# untitled.net
KiCad netlist of a schematic drawn in EAGLE
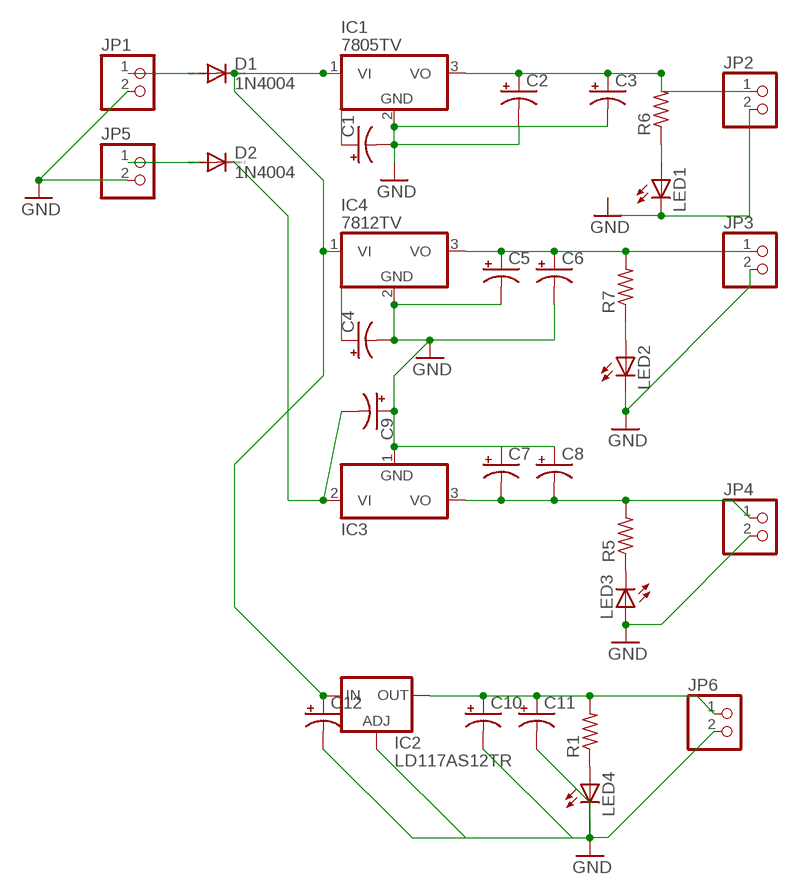
[diagram p0: schematic, sheet 1]

(export (version "E")
  (design (tool "Eeschema 10.0.6"))
  (components
    (comp (ref "C1")
      (value "CPOL-USE2.5-5")
      (footprint "eagle-import:E2,5-5")
      (libsource (lib "eagle-import") (part "CPOL-USE2.5-5"))
    )
    (comp (ref "C2")
      (value "CPOL-USE2.5-5")
      (footprint "eagle-import:E2,5-5")
      (libsource (lib "eagle-import") (part "CPOL-USE2.5-5"))
    )
    (comp (ref "C3")
      (value "CPOL-USE2.5-5")
      (footprint "eagle-import:E2,5-5")
      (libsource (lib "eagle-import") (part "CPOL-USE2.5-5"))
    )
    (comp (ref "C4")
      (value "CPOL-USE2.5-5")
      (footprint "eagle-import:E2,5-5")
      (libsource (lib "eagle-import") (part "CPOL-USE2.5-5"))
    )
    (comp (ref "C5")
      (value "CPOL-USE2.5-5")
      (footprint "eagle-import:E2,5-5")
      (libsource (lib "eagle-import") (part "CPOL-USE2.5-5"))
    )
    (comp (ref "C6")
      (value "CPOL-USE2.5-5")
      (footprint "eagle-import:E2,5-5")
      (libsource (lib "eagle-import") (part "CPOL-USE2.5-5"))
    )
    (comp (ref "C7")
      (value "CPOL-USE2.5-5")
      (footprint "eagle-import:E2,5-5")
      (libsource (lib "eagle-import") (part "CPOL-USE2.5-5"))
    )
    (comp (ref "C8")
      (value "CPOL-USE2.5-5")
      (footprint "eagle-import:E2,5-5")
      (libsource (lib "eagle-import") (part "CPOL-USE2.5-5"))
    )
    (comp (ref "C9")
      (value "CPOL-USE2.5-5")
      (footprint "eagle-import:E2,5-5")
      (libsource (lib "eagle-import") (part "CPOL-USE2.5-5"))
    )
    (comp (ref "C10")
      (value "CPOL-USE2.5-5")
      (footprint "eagle-import:E2,5-5")
      (libsource (lib "eagle-import") (part "CPOL-USE2.5-5"))
    )
    (comp (ref "C11")
      (value "CPOL-USE2.5-5")
      (footprint "eagle-import:E2,5-5")
      (libsource (lib "eagle-import") (part "CPOL-USE2.5-5"))
    )
    (comp (ref "C12")
      (value "CPOL-USE2.5-5")
      (footprint "eagle-import:E2,5-5")
      (libsource (lib "eagle-import") (part "CPOL-USE2.5-5"))
    )
    (comp (ref "D1")
      (value "1N4004")
      (footprint "eagle-import:DO41-10")
      (libsource (lib "eagle-import") (part "1N4004"))
    )
    (comp (ref "D2")
      (value "1N4004")
      (footprint "eagle-import:DO41-10")
      (libsource (lib "eagle-import") (part "1N4004"))
    )
    (comp (ref "IC1")
      (value "7805TV")
      (footprint "eagle-import:TO220V")
      (libsource (lib "eagle-import") (part "78TV05"))
    )
    (comp (ref "IC2")
      (value "LD117AS12TR")
      (footprint "eagle-import:SOT223")
      (libsource (lib "eagle-import") (part "LD117A?S12TR"))
    )
    (comp (ref "IC3")
      (value "7912T")
      (footprint "eagle-import:TO220H")
      (libsource (lib "eagle-import") (part "79T12"))
    )
    (comp (ref "IC4")
      (value "7812TV")
      (footprint "eagle-import:TO220V")
      (libsource (lib "eagle-import") (part "78TV12"))
    )
    (comp (ref "JP1")
      (value "PINHD-1X2")
      (footprint "eagle-import:1X02")
      (libsource (lib "eagle-import") (part "PINHD-1X2"))
    )
    (comp (ref "JP2")
      (value "PINHD-1X2")
      (footprint "eagle-import:1X02")
      (libsource (lib "eagle-import") (part "PINHD-1X2"))
    )
    (comp (ref "JP3")
      (value "PINHD-1X2")
      (footprint "eagle-import:1X02")
      (libsource (lib "eagle-import") (part "PINHD-1X2"))
    )
    (comp (ref "JP4")
      (value "PINHD-1X2")
      (footprint "eagle-import:1X02")
      (libsource (lib "eagle-import") (part "PINHD-1X2"))
    )
    (comp (ref "JP5")
      (value "PINHD-1X2")
      (footprint "eagle-import:1X02")
      (libsource (lib "eagle-import") (part "PINHD-1X2"))
    )
    (comp (ref "JP6")
      (value "PINHD-1X2")
      (footprint "eagle-import:1X02")
      (libsource (lib "eagle-import") (part "PINHD-1X2"))
    )
    (comp (ref "LED1")
      (value "LED3MM")
      (footprint "eagle-import:LED3MM")
      (libsource (lib "eagle-import") (part "LED3MM"))
    )
    (comp (ref "LED2")
      (value "LED3MM")
      (footprint "eagle-import:LED3MM")
      (libsource (lib "eagle-import") (part "LED3MM"))
    )
    (comp (ref "LED3")
      (value "LED3MM")
      (footprint "eagle-import:LED3MM")
      (libsource (lib "eagle-import") (part "LED3MM"))
    )
    (comp (ref "LED4")
      (value "LED3MM")
      (footprint "eagle-import:LED3MM")
      (libsource (lib "eagle-import") (part "LED3MM"))
    )
    (comp (ref "R1")
      (value "R-US_R1206")
      (footprint "eagle-import:R1206")
      (libsource (lib "eagle-import") (part "R-US_R1206"))
    )
    (comp (ref "R5")
      (value "R-US_R1206")
      (footprint "eagle-import:R1206")
      (libsource (lib "eagle-import") (part "R-US_R1206"))
    )
    (comp (ref "R6")
      (value "R-US_R1206")
      (footprint "eagle-import:R1206")
      (libsource (lib "eagle-import") (part "R-US_R1206"))
    )
    (comp (ref "R7")
      (value "R-US_R1206")
      (footprint "eagle-import:R1206")
      (libsource (lib "eagle-import") (part "R-US_R1206"))
    )
  )
  (nets
    (net (code "1") (name "GND") (class "Default")
      (node (ref "C1") (pin "-") (pinfunction "-_-") (pintype "passive"))
      (node (ref "C10") (pin "-") (pinfunction "-_-") (pintype "passive"))
      (node (ref "C11") (pin "-") (pinfunction "-_-") (pintype "passive"))
      (node (ref "C12") (pin "-") (pinfunction "-_-") (pintype "passive"))
      (node (ref "C2") (pin "-") (pinfunction "-_-") (pintype "passive"))
      (node (ref "C3") (pin "-") (pinfunction "-_-") (pintype "passive"))
      (node (ref "C4") (pin "-") (pinfunction "-_-") (pintype "passive"))
      (node (ref "C5") (pin "-") (pinfunction "-_-") (pintype "passive"))
      (node (ref "C6") (pin "-") (pinfunction "-_-") (pintype "passive"))
      (node (ref "C7") (pin "+") (pinfunction "+_+") (pintype "passive"))
      (node (ref "C8") (pin "+") (pinfunction "+_+") (pintype "passive"))
      (node (ref "C9") (pin "+") (pinfunction "+_+") (pintype "passive"))
      (node (ref "IC1") (pin "2") (pinfunction "GND_2") (pintype "passive"))
      (node (ref "IC2") (pin "1") (pinfunction "ADJ_1") (pintype "input"))
      (node (ref "IC3") (pin "1") (pinfunction "GND_1") (pintype "passive"))
      (node (ref "IC4") (pin "2") (pinfunction "GND_2") (pintype "passive"))
      (node (ref "JP1") (pin "2") (pinfunction "2_2") (pintype "passive"))
      (node (ref "JP2") (pin "2") (pinfunction "2_2") (pintype "passive"))
      (node (ref "JP3") (pin "2") (pinfunction "2_2") (pintype "passive"))
      (node (ref "JP4") (pin "2") (pinfunction "2_2") (pintype "passive"))
      (node (ref "JP5") (pin "2") (pinfunction "2_2") (pintype "passive"))
      (node (ref "JP6") (pin "2") (pinfunction "2_2") (pintype "passive"))
      (node (ref "LED1") (pin "K") (pinfunction "C_K") (pintype "passive"))
      (node (ref "LED2") (pin "K") (pinfunction "C_K") (pintype "passive"))
      (node (ref "LED3") (pin "A") (pinfunction "A_A") (pintype "passive"))
      (node (ref "LED4") (pin "K") (pinfunction "C_K") (pintype "passive"))
    )
    (net (code "2") (name "Net-(D1-PadA)") (class "Default")
      (node (ref "D1") (pin "A") (pinfunction "A_A") (pintype "passive"))
      (node (ref "JP1") (pin "1") (pinfunction "1_1") (pintype "passive"))
    )
    (net (code "3") (name "Net-(D2-PadA)") (class "Default")
      (node (ref "D2") (pin "A") (pinfunction "A_A") (pintype "passive"))
      (node (ref "JP5") (pin "1") (pinfunction "1_1") (pintype "passive"))
    )
    (net (code "4") (name "Net-(IC1-VI)") (class "Default")
      (node (ref "C1") (pin "+") (pinfunction "+_+") (pintype "passive"))
      (node (ref "C12") (pin "+") (pinfunction "+_+") (pintype "passive"))
      (node (ref "C4") (pin "+") (pinfunction "+_+") (pintype "passive"))
      (node (ref "D1") (pin "C") (pinfunction "C_C") (pintype "passive"))
      (node (ref "IC1") (pin "1") (pinfunction "VI_1") (pintype "input"))
      (node (ref "IC2") (pin "3") (pinfunction "IN_3") (pintype "input"))
      (node (ref "IC4") (pin "1") (pinfunction "VI_1") (pintype "input"))
    )
    (net (code "5") (name "Net-(IC1-VO)") (class "Default")
      (node (ref "C2") (pin "+") (pinfunction "+_+") (pintype "passive"))
      (node (ref "C3") (pin "+") (pinfunction "+_+") (pintype "passive"))
      (node (ref "IC1") (pin "3") (pinfunction "VO_3") (pintype "passive"))
      (node (ref "JP2") (pin "1") (pinfunction "1_1") (pintype "passive"))
      (node (ref "R6") (pin "2") (pinfunction "2_2") (pintype "passive"))
    )
    (net (code "6") (name "Net-(IC2-OUT)") (class "Default")
      (node (ref "C10") (pin "+") (pinfunction "+_+") (pintype "passive"))
      (node (ref "C11") (pin "+") (pinfunction "+_+") (pintype "passive"))
      (node (ref "IC2") (pin "4") (pinfunction "OUT_4") (pintype "passive"))
      (node (ref "JP6") (pin "1") (pinfunction "1_1") (pintype "passive"))
      (node (ref "R1") (pin "2") (pinfunction "2_2") (pintype "passive"))
    )
    (net (code "7") (name "Net-(IC3-VI)") (class "Default")
      (node (ref "C9") (pin "-") (pinfunction "-_-") (pintype "passive"))
      (node (ref "D2") (pin "C") (pinfunction "C_C") (pintype "passive"))
      (node (ref "IC3") (pin "2") (pinfunction "VI_2") (pintype "input"))
    )
    (net (code "8") (name "Net-(IC3-VO)") (class "Default")
      (node (ref "C7") (pin "-") (pinfunction "-_-") (pintype "passive"))
      (node (ref "C8") (pin "-") (pinfunction "-_-") (pintype "passive"))
      (node (ref "IC3") (pin "3") (pinfunction "VO_3") (pintype "passive"))
      (node (ref "JP4") (pin "1") (pinfunction "1_1") (pintype "passive"))
      (node (ref "R5") (pin "2") (pinfunction "2_2") (pintype "passive"))
    )
    (net (code "9") (name "Net-(IC4-VO)") (class "Default")
      (node (ref "C5") (pin "+") (pinfunction "+_+") (pintype "passive"))
      (node (ref "C6") (pin "+") (pinfunction "+_+") (pintype "passive"))
      (node (ref "IC4") (pin "3") (pinfunction "VO_3") (pintype "passive"))
      (node (ref "JP3") (pin "1") (pinfunction "1_1") (pintype "passive"))
      (node (ref "R7") (pin "2") (pinfunction "2_2") (pintype "passive"))
    )
    (net (code "10") (name "Net-(LED1-PadA)") (class "Default")
      (node (ref "LED1") (pin "A") (pinfunction "A_A") (pintype "passive"))
      (node (ref "R6") (pin "1") (pinfunction "1_1") (pintype "passive"))
    )
    (net (code "11") (name "Net-(LED2-PadA)") (class "Default")
      (node (ref "LED2") (pin "A") (pinfunction "A_A") (pintype "passive"))
      (node (ref "R7") (pin "1") (pinfunction "1_1") (pintype "passive"))
    )
    (net (code "12") (name "Net-(LED3-C)") (class "Default")
      (node (ref "LED3") (pin "K") (pinfunction "C_K") (pintype "passive"))
      (node (ref "R5") (pin "1") (pinfunction "1_1") (pintype "passive"))
    )
    (net (code "13") (name "Net-(LED4-PadA)") (class "Default")
      (node (ref "LED4") (pin "A") (pinfunction "A_A") (pintype "passive"))
      (node (ref "R1") (pin "1") (pinfunction "1_1") (pintype "passive"))
    )
  )
)
